# 08-Clock.net
KiCad netlist of a schematic drawn in Altium Designer
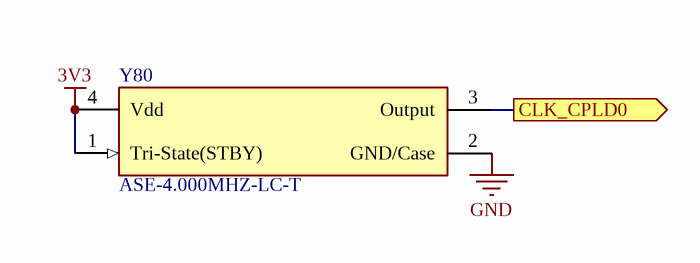
[diagram p0: 08-Clock.SchDoc]

(export (version "E")
  (design (tool "Eeschema 10.0.6"))
  (components
    (comp (ref "Y80")
      (value "ASE-4.000MHZ-LC-T")
      (footprint "ASE-4.000MHZ-LC-T_HandSoldering")
      (description "XTAL OSC XO 4.0000MHZ CMOS SMD")
      (libsource (lib "Schlib_EES") (part "OC_SMD_4MHz_3V3_ASE"))
    )
  )
  (nets
    (net (code "1") (name "/CLK_CPLD0") (class "Default")
      (node (ref "Y80") (pin "3") (pinfunction "Output_3") (pintype "passive"))
    )
    (net (code "2") (name "3V3") (class "Default")
      (node (ref "Y80") (pin "1") (pinfunction "Tri-State(STBY)_1") (pintype "input"))
      (node (ref "Y80") (pin "4") (pinfunction "Vdd_4") (pintype "power_in"))
    )
    (net (code "3") (name "GND") (class "Default")
      (node (ref "Y80") (pin "2") (pinfunction "GND/Case_2") (pintype "power_in"))
    )
  )
)
